# TIDA-PowerNB_BuckBoost.net
KiCad netlist of a schematic drawn in Altium Designer
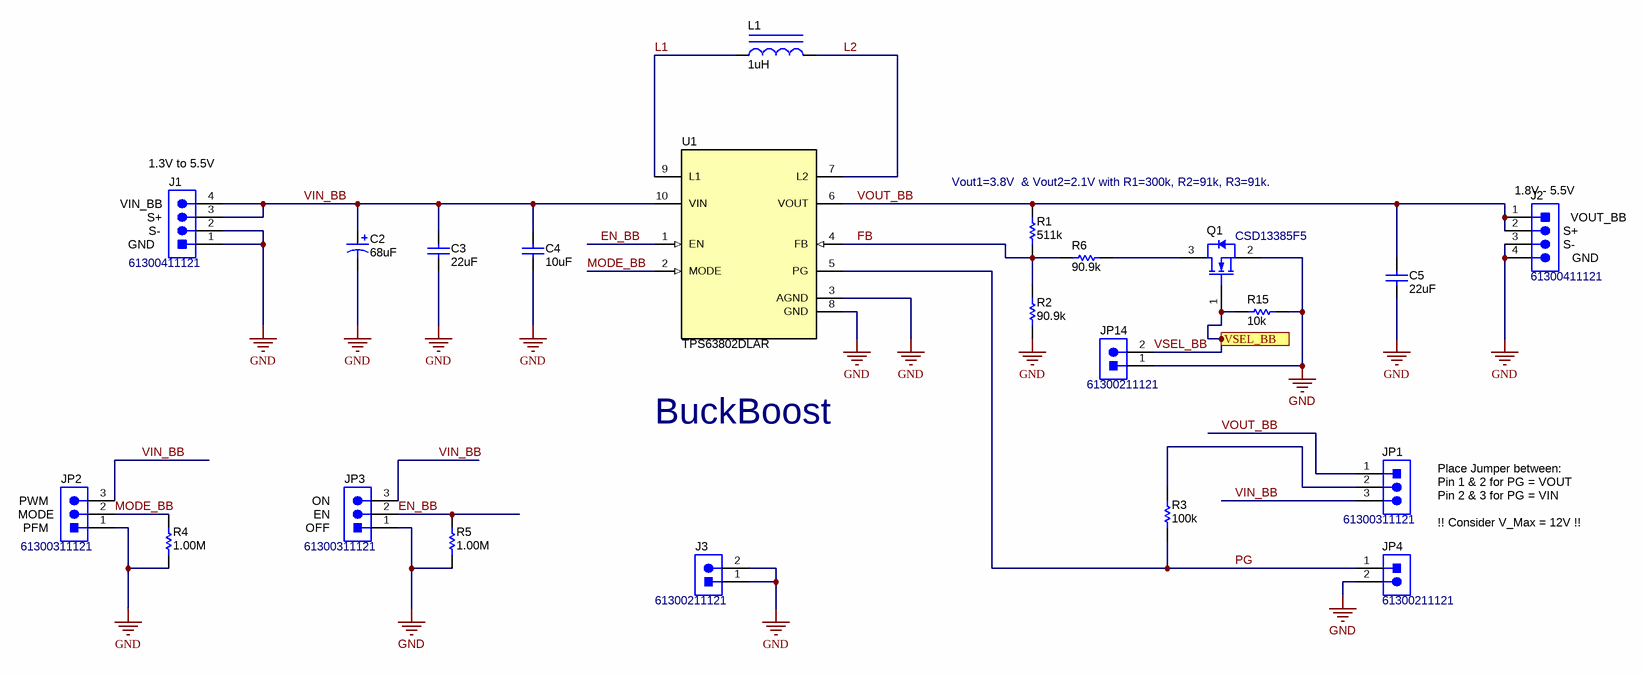
[diagram p0: TIDA-PowerNB_BuckBoost.SchDoc]

(export (version "E")
  (design (tool "Eeschema 10.0.6"))
  (components
    (comp (ref "C2")
      (value "Cap_Polarized")
      (footprint "7343-31")
      (description "CAP, TA, 68 uF, 20 V, +/- 10%, 0.15 ohm, SMD")
      (fields
        (field (name "PARTNUMBER") "T495D686K020ATE150")
        (field (name "VALUEDISPLAYED") "68uF")
        (field (name "MANUFACTURER") "Kemet")
        (field (name "PUBLISHER") "Texas Instruments")
      )
      (libsource (lib "Altium Vault - TI") (part "Cap_Polarized"))
    )
    (comp (ref "C3")
      (value "Capacitor")
      (footprint "1206_190")
      (description "CAP, CERM, 22 uF, 25 V, +/- 20%, X5R, 1206_190")
      (fields
        (field (name "PARTNUMBER") "TMK316BBJ226ML-T")
        (field (name "VALUEDISPLAYED") "22uF")
        (field (name "MANUFACTURER") "Taiyo Yuden")
        (field (name "PUBLISHER") "Texas Instruments")
      )
      (libsource (lib "Altium Vault - TI") (part "Capacitor"))
    )
    (comp (ref "C4")
      (value "Capacitor")
      (footprint "0603S")
      (description "CAP, CERM, 10 uF, 6.3 V, +/- 20%, X5R, 0603")
      (fields
        (field (name "PARTNUMBER") "GRM188R60J106ME84")
        (field (name "VALUEDISPLAYED") "10uF")
        (field (name "MANUFACTURER") "MuRata")
        (field (name "PUBLISHER") "Texas Instruments")
      )
      (libsource (lib "Altium Vault - TI") (part "Capacitor"))
    )
    (comp (ref "C5")
      (value "Capacitor")
      (footprint "0603S")
      (description "CAP, CERM, 22 uF, 6.3 V, +/- 20%, X5R, 0603")
      (fields
        (field (name "PARTNUMBER") "GRM188R60J226MEA0D")
        (field (name "VALUEDISPLAYED") "22uF")
        (field (name "MANUFACTURER") "MuRata")
        (field (name "PUBLISHER") "Texas Instruments")
      )
      (libsource (lib "Altium Vault - TI") (part "CMP-0007306-5"))
    )
    (comp (ref "J1")
      (value "61300411121")
      (footprint "WURTH_61300411121")
      (description "Header, 2.54 mm, 4x1, Gold, TH")
      (fields (field (name "MANUFACTURER") "Wurth Elektronik"))
      (libsource (lib "") (part "Header_4x1_1"))
    )
    (comp (ref "J2")
      (value "61300411121")
      (footprint "WURTH_61300411121")
      (description "Header, 2.54 mm, 4x1, Gold, TH")
      (fields (field (name "MANUFACTURER") "Wurth Elektronik"))
      (libsource (lib "Altium Vault - TI") (part "Header_4x1"))
    )
    (comp (ref "J3")
      (value "61300211121")
      (footprint "WURTH_61300211121")
      (description "Header, 2.54 mm, 2x1, Gold, TH")
      (fields (field (name "MANUFACTURER") "Wurth Elektronik"))
      (libsource (lib "Altium Vault - TI") (part "Header_2x1"))
    )
    (comp (ref "JP1")
      (value "61300311121")
      (footprint "WURTH_61300311121")
      (description "Header, 2.54 mm, 3x1, Gold, TH")
      (fields (field (name "MANUFACTURER") "Wurth Elektronik"))
      (libsource (lib "") (part "Header_3x1_1"))
    )
    (comp (ref "JP2")
      (value "61300311121")
      (footprint "WURTH_61300311121")
      (description "Header, 2.54 mm, 3x1, Gold, TH")
      (fields (field (name "MANUFACTURER") "Wurth Elektronik"))
      (libsource (lib "Altium Vault - TI") (part "Header_3x1"))
    )
    (comp (ref "JP3")
      (value "61300311121")
      (footprint "WURTH_61300311121")
      (description "Header, 2.54 mm, 3x1, Gold, TH")
      (fields (field (name "MANUFACTURER") "Wurth Elektronik"))
      (libsource (lib "Altium Vault - TI") (part "Header_3x1"))
    )
    (comp (ref "JP4")
      (value "61300211121")
      (footprint "WURTH_61300211121")
      (description "Header, 2.54 mm, 2x1, Gold, TH")
      (fields (field (name "MANUFACTURER") "Wurth Elektronik"))
      (libsource (lib "") (part "Header_2x1_1"))
    )
    (comp (ref "JP14")
      (value "61300211121")
      (footprint "WURTH_61300211121")
      (description "Header, 2.54 mm, 2x1, Gold, TH")
      (fields (field (name "MANUFACTURER") "Wurth Elektronik"))
      (libsource (lib "Altium Vault - TI") (part "Header_2x1"))
    )
    (comp (ref "L1")
      (value "74438356010")
      (footprint "WE-MAPI_4020")
      (description "Inductor, Shielded, 1 uH, 7.2 A, 0.012 ohm, SMD")
      (fields
        (field (name "MANUFACTURER") "Wurth Elektronik")
        (field (name "VALUEDISPLAYED") "1uH")
        (field (name "PUBLISHER") "Texas Instruments")
      )
      (libsource (lib "Altium Vault - TI") (part "Inductor_Iron"))
    )
    (comp (ref "Q1")
      (value "CSD13385F5")
      (footprint "YJK0003A")
      (description "MOSFET, N-CH, 12 V, 4.3 A, YJK0003A (PICOSTAR-3)")
      (fields (field (name "MANUFACTURER") "Texas Instruments"))
      (libsource (lib "Altium Vault - TI") (part "MOSFET_N_D3G1S2"))
    )
    (comp (ref "R1")
      (value "CRCW0402511KFKED")
      (footprint "0402")
      (description "RES, 511 k, 1%, 0.063 W, AEC-Q200 Grade 0, 0402")
      (fields (field (name "MANUFACTURER") "Vishay-Dale") (field (name "VALUEDISPLAYED") "511k"))
      (libsource (lib "Altium Vault - TI") (part "Resistor"))
    )
    (comp (ref "R2")
      (value "CRCW040290K9FKED")
      (footprint "0402")
      (description "RES, 90.9 k, 1%, 0.063 W, AEC-Q200 Grade 0, 0402")
      (fields (field (name "MANUFACTURER") "Vishay-Dale") (field (name "VALUEDISPLAYED") "90.9k"))
      (libsource (lib "Altium Vault - TI") (part "Resistor"))
    )
    (comp (ref "R3")
      (value "RC0402FR-07100KL")
      (footprint "0402")
      (description "RES, 100 k, 1%, 0.0625 W, 0402")
      (fields
        (field (name "MANUFACTURER") "Yageo America")
        (field (name "VALUEDISPLAYED") "100k")
        (field (name "PUBLISHER") "Texas Instruments")
      )
      (libsource (lib "Altium Vault - TI") (part "Resistor"))
    )
    (comp (ref "R4")
      (value "CRCW04021M00FKED")
      (footprint "0402")
      (description "RES, 1.00 M, 1%, 0.063 W, AEC-Q200 Grade 0, 0402")
      (fields (field (name "MANUFACTURER") "Vishay-Dale") (field (name "VALUEDISPLAYED") "1.00M"))
      (libsource (lib "Altium Vault - TI") (part "Resistor"))
    )
    (comp (ref "R5")
      (value "CRCW04021M00FKED")
      (footprint "0402")
      (description "RES, 1.00 M, 1%, 0.063 W, AEC-Q200 Grade 0, 0402")
      (fields (field (name "MANUFACTURER") "Vishay-Dale") (field (name "VALUEDISPLAYED") "1.00M"))
      (libsource (lib "Altium Vault - TI") (part "Resistor"))
    )
    (comp (ref "R6")
      (value "CRCW040290K9FKED")
      (footprint "0402")
      (description "RES, 90.9 k, 1%, 0.063 W, AEC-Q200 Grade 0, 0402")
      (fields (field (name "MANUFACTURER") "Vishay-Dale") (field (name "VALUEDISPLAYED") "90.9k"))
      (libsource (lib "Altium Vault - TI") (part "Resistor"))
    )
    (comp (ref "R15")
      (value "ERJ-2RKF1002X")
      (footprint "0402")
      (description "RES, 10.0 k, 1%, 0.1 W, 0402")
      (fields
        (field (name "MANUFACTURER") "Panasonic")
        (field (name "RES_OHM") "10k")
        (field (name "PUBLISHER") "Texas Instruments")
      )
      (libsource (lib "Altium Vault - TI") (part "CMP-0026658-1"))
    )
    (comp (ref "U1")
      (value "TPS63802DLAR")
      (footprint "DLA0010A")
      (description "High Current, High Efficiency Single Inductor Buck-Boost Converter, DLA0010A (VQFN-HR-10)")
      (fields
        (field (name "PARTNUMBER") "TPS63802DLAR")
        (field (name "MANUFACTURER") "Texas Instruments")
        (field (name "ALTERNATE PARTNUMBER") "TPS63802DLAT")
        (field (name "PUBLISHER") "Texas Instruments")
      )
      (libsource (lib "Altium Vault - TI") (part "TPS63802DLA"))
    )
  )
  (nets
    (net (code "1") (name "/EN_BB") (class "Default")
      (node (ref "JP3") (pin "2") (pinfunction "2_2") (pintype "passive"))
      (node (ref "R5") (pin "2") (pinfunction "2_2") (pintype "passive"))
      (node (ref "U1") (pin "1") (pinfunction "EN_1") (pintype "input"))
    )
    (net (code "2") (name "/FB") (class "Default")
      (node (ref "R1") (pin "1") (pinfunction "1_1") (pintype "passive"))
      (node (ref "R2") (pin "2") (pinfunction "2_2") (pintype "passive"))
      (node (ref "R6") (pin "2") (pinfunction "2_2") (pintype "passive"))
      (node (ref "U1") (pin "4") (pinfunction "FB_4") (pintype "input"))
    )
    (net (code "3") (name "/L1") (class "Default")
      (node (ref "L1") (pin "1") (pinfunction "1_1") (pintype "passive"))
      (node (ref "U1") (pin "9") (pinfunction "L1_9") (pintype "passive"))
    )
    (net (code "4") (name "/L2") (class "Default")
      (node (ref "L1") (pin "2") (pinfunction "2_2") (pintype "passive"))
      (node (ref "U1") (pin "7") (pinfunction "L2_7") (pintype "passive"))
    )
    (net (code "5") (name "/MODE_BB") (class "Default")
      (node (ref "JP2") (pin "2") (pinfunction "2_2") (pintype "passive"))
      (node (ref "R4") (pin "2") (pinfunction "2_2") (pintype "passive"))
      (node (ref "U1") (pin "2") (pinfunction "MODE_2") (pintype "input"))
    )
    (net (code "6") (name "/PG") (class "Default")
      (node (ref "JP4") (pin "1") (pinfunction "1_1") (pintype "passive"))
      (node (ref "R3") (pin "1") (pinfunction "1_1") (pintype "passive"))
      (node (ref "U1") (pin "5") (pinfunction "PG_5") (pintype "open_collector"))
    )
    (net (code "7") (name "/VIN_BB") (class "Default")
      (node (ref "C2") (pin "1") (pinfunction "+_1") (pintype "passive"))
      (node (ref "C3") (pin "1") (pinfunction "1_1") (pintype "passive"))
      (node (ref "C4") (pin "1") (pinfunction "1_1") (pintype "passive"))
      (node (ref "J1") (pin "3") (pinfunction "3_3") (pintype "passive"))
      (node (ref "J1") (pin "4") (pinfunction "4_4") (pintype "passive"))
      (node (ref "JP1") (pin "3") (pinfunction "3_3") (pintype "passive"))
      (node (ref "JP2") (pin "3") (pinfunction "3_3") (pintype "passive"))
      (node (ref "JP3") (pin "3") (pinfunction "3_3") (pintype "passive"))
      (node (ref "U1") (pin "10") (pinfunction "VIN_10") (pintype "power_in"))
    )
    (net (code "8") (name "/VOUT_BB") (class "Default")
      (node (ref "C5") (pin "1") (pinfunction "1_1") (pintype "passive"))
      (node (ref "J2") (pin "1") (pinfunction "1_1") (pintype "passive"))
      (node (ref "J2") (pin "2") (pinfunction "2_2") (pintype "passive"))
      (node (ref "JP1") (pin "1") (pinfunction "1_1") (pintype "passive"))
      (node (ref "R1") (pin "2") (pinfunction "2_2") (pintype "passive"))
      (node (ref "U1") (pin "6") (pinfunction "VOUT_6") (pintype "power_in"))
    )
    (net (code "9") (name "/VSEL_BB") (class "Default")
      (node (ref "JP14") (pin "2") (pinfunction "2_2") (pintype "passive"))
      (node (ref "Q1") (pin "1") (pinfunction "G_1") (pintype "passive"))
      (node (ref "R15") (pin "2") (pinfunction "2_2") (pintype "passive"))
    )
    (net (code "10") (name "GND") (class "Default")
      (node (ref "C2") (pin "2") (pinfunction "-_2") (pintype "passive"))
      (node (ref "C3") (pin "2") (pinfunction "2_2") (pintype "passive"))
      (node (ref "C4") (pin "2") (pinfunction "2_2") (pintype "passive"))
      (node (ref "C5") (pin "2") (pinfunction "2_2") (pintype "passive"))
      (node (ref "J1") (pin "1") (pinfunction "1_1") (pintype "passive"))
      (node (ref "J1") (pin "2") (pinfunction "2_2") (pintype "passive"))
      (node (ref "J2") (pin "3") (pinfunction "3_3") (pintype "passive"))
      (node (ref "J2") (pin "4") (pinfunction "4_4") (pintype "passive"))
      (node (ref "J3") (pin "1") (pinfunction "1_1") (pintype "passive"))
      (node (ref "J3") (pin "2") (pinfunction "2_2") (pintype "passive"))
      (node (ref "JP14") (pin "1") (pinfunction "1_1") (pintype "passive"))
      (node (ref "JP2") (pin "1") (pinfunction "1_1") (pintype "passive"))
      (node (ref "JP3") (pin "1") (pinfunction "1_1") (pintype "passive"))
      (node (ref "JP4") (pin "2") (pinfunction "2_2") (pintype "passive"))
      (node (ref "Q1") (pin "2") (pinfunction "S_2") (pintype "passive"))
      (node (ref "R15") (pin "1") (pinfunction "1_1") (pintype "passive"))
      (node (ref "R2") (pin "1") (pinfunction "1_1") (pintype "passive"))
      (node (ref "R4") (pin "1") (pinfunction "1_1") (pintype "passive"))
      (node (ref "R5") (pin "1") (pinfunction "1_1") (pintype "passive"))
      (node (ref "U1") (pin "3") (pinfunction "AGND_3") (pintype "power_in"))
      (node (ref "U1") (pin "8") (pinfunction "GND_8") (pintype "power_in"))
    )
    (net (code "11") (name "Net-(JP1-Pad2)") (class "Default")
      (node (ref "JP1") (pin "2") (pinfunction "2_2") (pintype "passive"))
      (node (ref "R3") (pin "2") (pinfunction "2_2") (pintype "passive"))
    )
    (net (code "12") (name "Net-(Q1-D)") (class "Default")
      (node (ref "Q1") (pin "3") (pinfunction "D_3") (pintype "passive"))
      (node (ref "R6") (pin "1") (pinfunction "1_1") (pintype "passive"))
    )
  )
)
